# Altium.net
KiCad netlist of a schematic drawn in Altium Designer
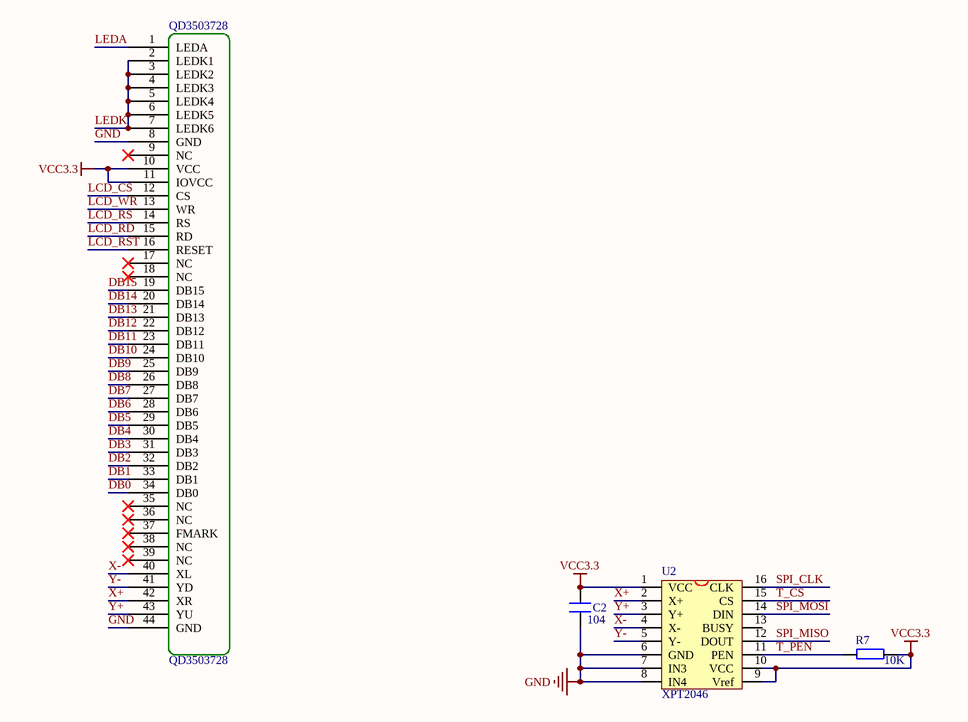
[diagram p0: 原理图(Altium).SchDoc]

(export (version "E")
  (design (tool "Eeschema 10.0.6"))
  (components
    (comp (ref "C2") (value "104") (footprint "C0603") (libsource (lib "战舰STM32开发板底板") (part "C")))
    (comp (ref "QD3503728")
      (value "QD3503728")
      (footprint "QD3503728")
      (libsource (lib "QD3503728_原理图封装库") (part "QD3503728"))
    )
    (comp (ref "R7") (value "10K") (footprint "R0603") (libsource (lib "战舰STM32开发板底板") (part "R")))
    (comp (ref "U2") (value "XPT2046") (footprint "SSOP16") (libsource (lib "液晶模块封装库") (part "ADS7843")))
  )
  (nets
    (net (code "1") (name "/DB0") (class "Default")
      (node (ref "QD3503728") (pin "34") (pinfunction "DB0_34") (pintype "passive"))
    )
    (net (code "2") (name "/DB1") (class "Default")
      (node (ref "QD3503728") (pin "33") (pinfunction "DB1_33") (pintype "passive"))
    )
    (net (code "3") (name "/DB2") (class "Default")
      (node (ref "QD3503728") (pin "32") (pinfunction "DB2_32") (pintype "passive"))
    )
    (net (code "4") (name "/DB3") (class "Default")
      (node (ref "QD3503728") (pin "31") (pinfunction "DB3_31") (pintype "passive"))
    )
    (net (code "5") (name "/DB4") (class "Default")
      (node (ref "QD3503728") (pin "30") (pinfunction "DB4_30") (pintype "passive"))
    )
    (net (code "6") (name "/DB5") (class "Default")
      (node (ref "QD3503728") (pin "29") (pinfunction "DB5_29") (pintype "passive"))
    )
    (net (code "7") (name "/DB6") (class "Default")
      (node (ref "QD3503728") (pin "28") (pinfunction "DB6_28") (pintype "passive"))
    )
    (net (code "8") (name "/DB7") (class "Default")
      (node (ref "QD3503728") (pin "27") (pinfunction "DB7_27") (pintype "passive"))
    )
    (net (code "9") (name "/DB8") (class "Default")
      (node (ref "QD3503728") (pin "26") (pinfunction "DB8_26") (pintype "passive"))
    )
    (net (code "10") (name "/DB9") (class "Default")
      (node (ref "QD3503728") (pin "25") (pinfunction "DB9_25") (pintype "passive"))
    )
    (net (code "11") (name "/DB10") (class "Default")
      (node (ref "QD3503728") (pin "24") (pinfunction "DB10_24") (pintype "passive"))
    )
    (net (code "12") (name "/DB11") (class "Default")
      (node (ref "QD3503728") (pin "23") (pinfunction "DB11_23") (pintype "passive"))
    )
    (net (code "13") (name "/DB12") (class "Default")
      (node (ref "QD3503728") (pin "22") (pinfunction "DB12_22") (pintype "passive"))
    )
    (net (code "14") (name "/DB13") (class "Default")
      (node (ref "QD3503728") (pin "21") (pinfunction "DB13_21") (pintype "passive"))
    )
    (net (code "15") (name "/DB14") (class "Default")
      (node (ref "QD3503728") (pin "20") (pinfunction "DB14_20") (pintype "passive"))
    )
    (net (code "16") (name "/DB15") (class "Default")
      (node (ref "QD3503728") (pin "19") (pinfunction "DB15_19") (pintype "passive"))
    )
    (net (code "17") (name "/LCD_CS") (class "Default")
      (node (ref "QD3503728") (pin "12") (pinfunction "CS_12") (pintype "passive"))
    )
    (net (code "18") (name "/LCD_RD") (class "Default")
      (node (ref "QD3503728") (pin "15") (pinfunction "RD_15") (pintype "passive"))
    )
    (net (code "19") (name "/LCD_RS") (class "Default")
      (node (ref "QD3503728") (pin "14") (pinfunction "RS_14") (pintype "passive"))
    )
    (net (code "20") (name "/LCD_RST") (class "Default")
      (node (ref "QD3503728") (pin "16") (pinfunction "RESET_16") (pintype "passive"))
    )
    (net (code "21") (name "/LCD_WR") (class "Default")
      (node (ref "QD3503728") (pin "13") (pinfunction "WR_13") (pintype "passive"))
    )
    (net (code "22") (name "/LEDA") (class "Default")
      (node (ref "QD3503728") (pin "1") (pinfunction "LEDA_1") (pintype "passive"))
    )
    (net (code "23") (name "/LEDK") (class "Default")
      (node (ref "QD3503728") (pin "2") (pinfunction "LEDK1_2") (pintype "passive"))
      (node (ref "QD3503728") (pin "3") (pinfunction "LEDK2_3") (pintype "passive"))
      (node (ref "QD3503728") (pin "4") (pinfunction "LEDK3_4") (pintype "passive"))
      (node (ref "QD3503728") (pin "5") (pinfunction "LEDK4_5") (pintype "passive"))
      (node (ref "QD3503728") (pin "6") (pinfunction "LEDK5_6") (pintype "passive"))
      (node (ref "QD3503728") (pin "7") (pinfunction "LEDK6_7") (pintype "passive"))
    )
    (net (code "24") (name "/SPI_CLK") (class "Default")
      (node (ref "U2") (pin "16") (pinfunction "CLK_16") (pintype "passive"))
    )
    (net (code "25") (name "/SPI_MISO") (class "Default")
      (node (ref "U2") (pin "12") (pinfunction "DOUT_12") (pintype "passive"))
    )
    (net (code "26") (name "/SPI_MOSI") (class "Default")
      (node (ref "U2") (pin "14") (pinfunction "DIN_14") (pintype "passive"))
    )
    (net (code "27") (name "/T_CS") (class "Default")
      (node (ref "U2") (pin "15") (pinfunction "CS_15") (pintype "passive"))
    )
    (net (code "28") (name "/T_PEN") (class "Default")
      (node (ref "R7") (pin "2") (pintype "passive"))
      (node (ref "U2") (pin "11") (pinfunction "PEN_11") (pintype "passive"))
    )
    (net (code "29") (name "/X+") (class "Default")
      (node (ref "QD3503728") (pin "42") (pinfunction "XR_42") (pintype "passive"))
      (node (ref "U2") (pin "2") (pinfunction "X+_2") (pintype "passive"))
    )
    (net (code "30") (name "/X-") (class "Default")
      (node (ref "QD3503728") (pin "40") (pinfunction "XL_40") (pintype "passive"))
      (node (ref "U2") (pin "4") (pinfunction "X-_4") (pintype "passive"))
    )
    (net (code "31") (name "/Y+") (class "Default")
      (node (ref "QD3503728") (pin "43") (pinfunction "YU_43") (pintype "passive"))
      (node (ref "U2") (pin "3") (pinfunction "Y+_3") (pintype "passive"))
    )
    (net (code "32") (name "/Y-") (class "Default")
      (node (ref "QD3503728") (pin "41") (pinfunction "YD_41") (pintype "passive"))
      (node (ref "U2") (pin "5") (pinfunction "Y-_5") (pintype "passive"))
    )
    (net (code "33") (name "GND") (class "Default")
      (node (ref "C2") (pin "2") (pintype "passive"))
      (node (ref "QD3503728") (pin "44") (pinfunction "GND_44") (pintype "passive"))
      (node (ref "QD3503728") (pin "8") (pinfunction "GND_8") (pintype "passive"))
      (node (ref "U2") (pin "6") (pinfunction "GND_6") (pintype "passive"))
      (node (ref "U2") (pin "7") (pinfunction "IN3_7") (pintype "passive"))
      (node (ref "U2") (pin "8") (pinfunction "IN4_8") (pintype "passive"))
    )
    (net (code "34") (name "VCC3.3") (class "Default")
      (node (ref "C2") (pin "1") (pintype "passive"))
      (node (ref "QD3503728") (pin "10") (pinfunction "VCC_10") (pintype "passive"))
      (node (ref "QD3503728") (pin "11") (pinfunction "IOVCC_11") (pintype "passive"))
      (node (ref "R7") (pin "1") (pintype "passive"))
      (node (ref "U2") (pin "1") (pinfunction "VCC_1") (pintype "passive"))
      (node (ref "U2") (pin "10") (pinfunction "VCC_10") (pintype "passive"))
      (node (ref "U2") (pin "9") (pinfunction "Vref_9") (pintype "passive"))
    )
    (net (code "35") (name "unconnected-(QD3503728-FMARK-Pad37)") (class "Default")
      (node (ref "QD3503728") (pin "37") (pinfunction "FMARK_37") (pintype "passive+no_connect"))
    )
    (net (code "36") (name "unconnected-(QD3503728-NC-Pad9)") (class "Default")
      (node (ref "QD3503728") (pin "9") (pinfunction "NC_9") (pintype "passive+no_connect"))
    )
    (net (code "37") (name "unconnected-(QD3503728-NC-Pad17)") (class "Default")
      (node (ref "QD3503728") (pin "17") (pinfunction "NC_17") (pintype "passive+no_connect"))
    )
    (net (code "38") (name "unconnected-(QD3503728-NC-Pad18)") (class "Default")
      (node (ref "QD3503728") (pin "18") (pinfunction "NC_18") (pintype "passive+no_connect"))
    )
    (net (code "39") (name "unconnected-(QD3503728-NC-Pad35)") (class "Default")
      (node (ref "QD3503728") (pin "35") (pinfunction "NC_35") (pintype "passive+no_connect"))
    )
    (net (code "40") (name "unconnected-(QD3503728-NC-Pad36)") (class "Default")
      (node (ref "QD3503728") (pin "36") (pinfunction "NC_36") (pintype "passive+no_connect"))
    )
    (net (code "41") (name "unconnected-(QD3503728-NC-Pad38)") (class "Default")
      (node (ref "QD3503728") (pin "38") (pinfunction "NC_38") (pintype "passive+no_connect"))
    )
    (net (code "42") (name "unconnected-(QD3503728-NC-Pad39)") (class "Default")
      (node (ref "QD3503728") (pin "39") (pinfunction "NC_39") (pintype "passive+no_connect"))
    )
    (net (code "43") (name "unconnected-(U2-BUSY-Pad13)") (class "Default")
      (node (ref "U2") (pin "13") (pinfunction "BUSY_13") (pintype "passive"))
    )
  )
)
